# ESP32_zigbee_zwaveV1.net
KiCad netlist of a schematic drawn in EAGLE
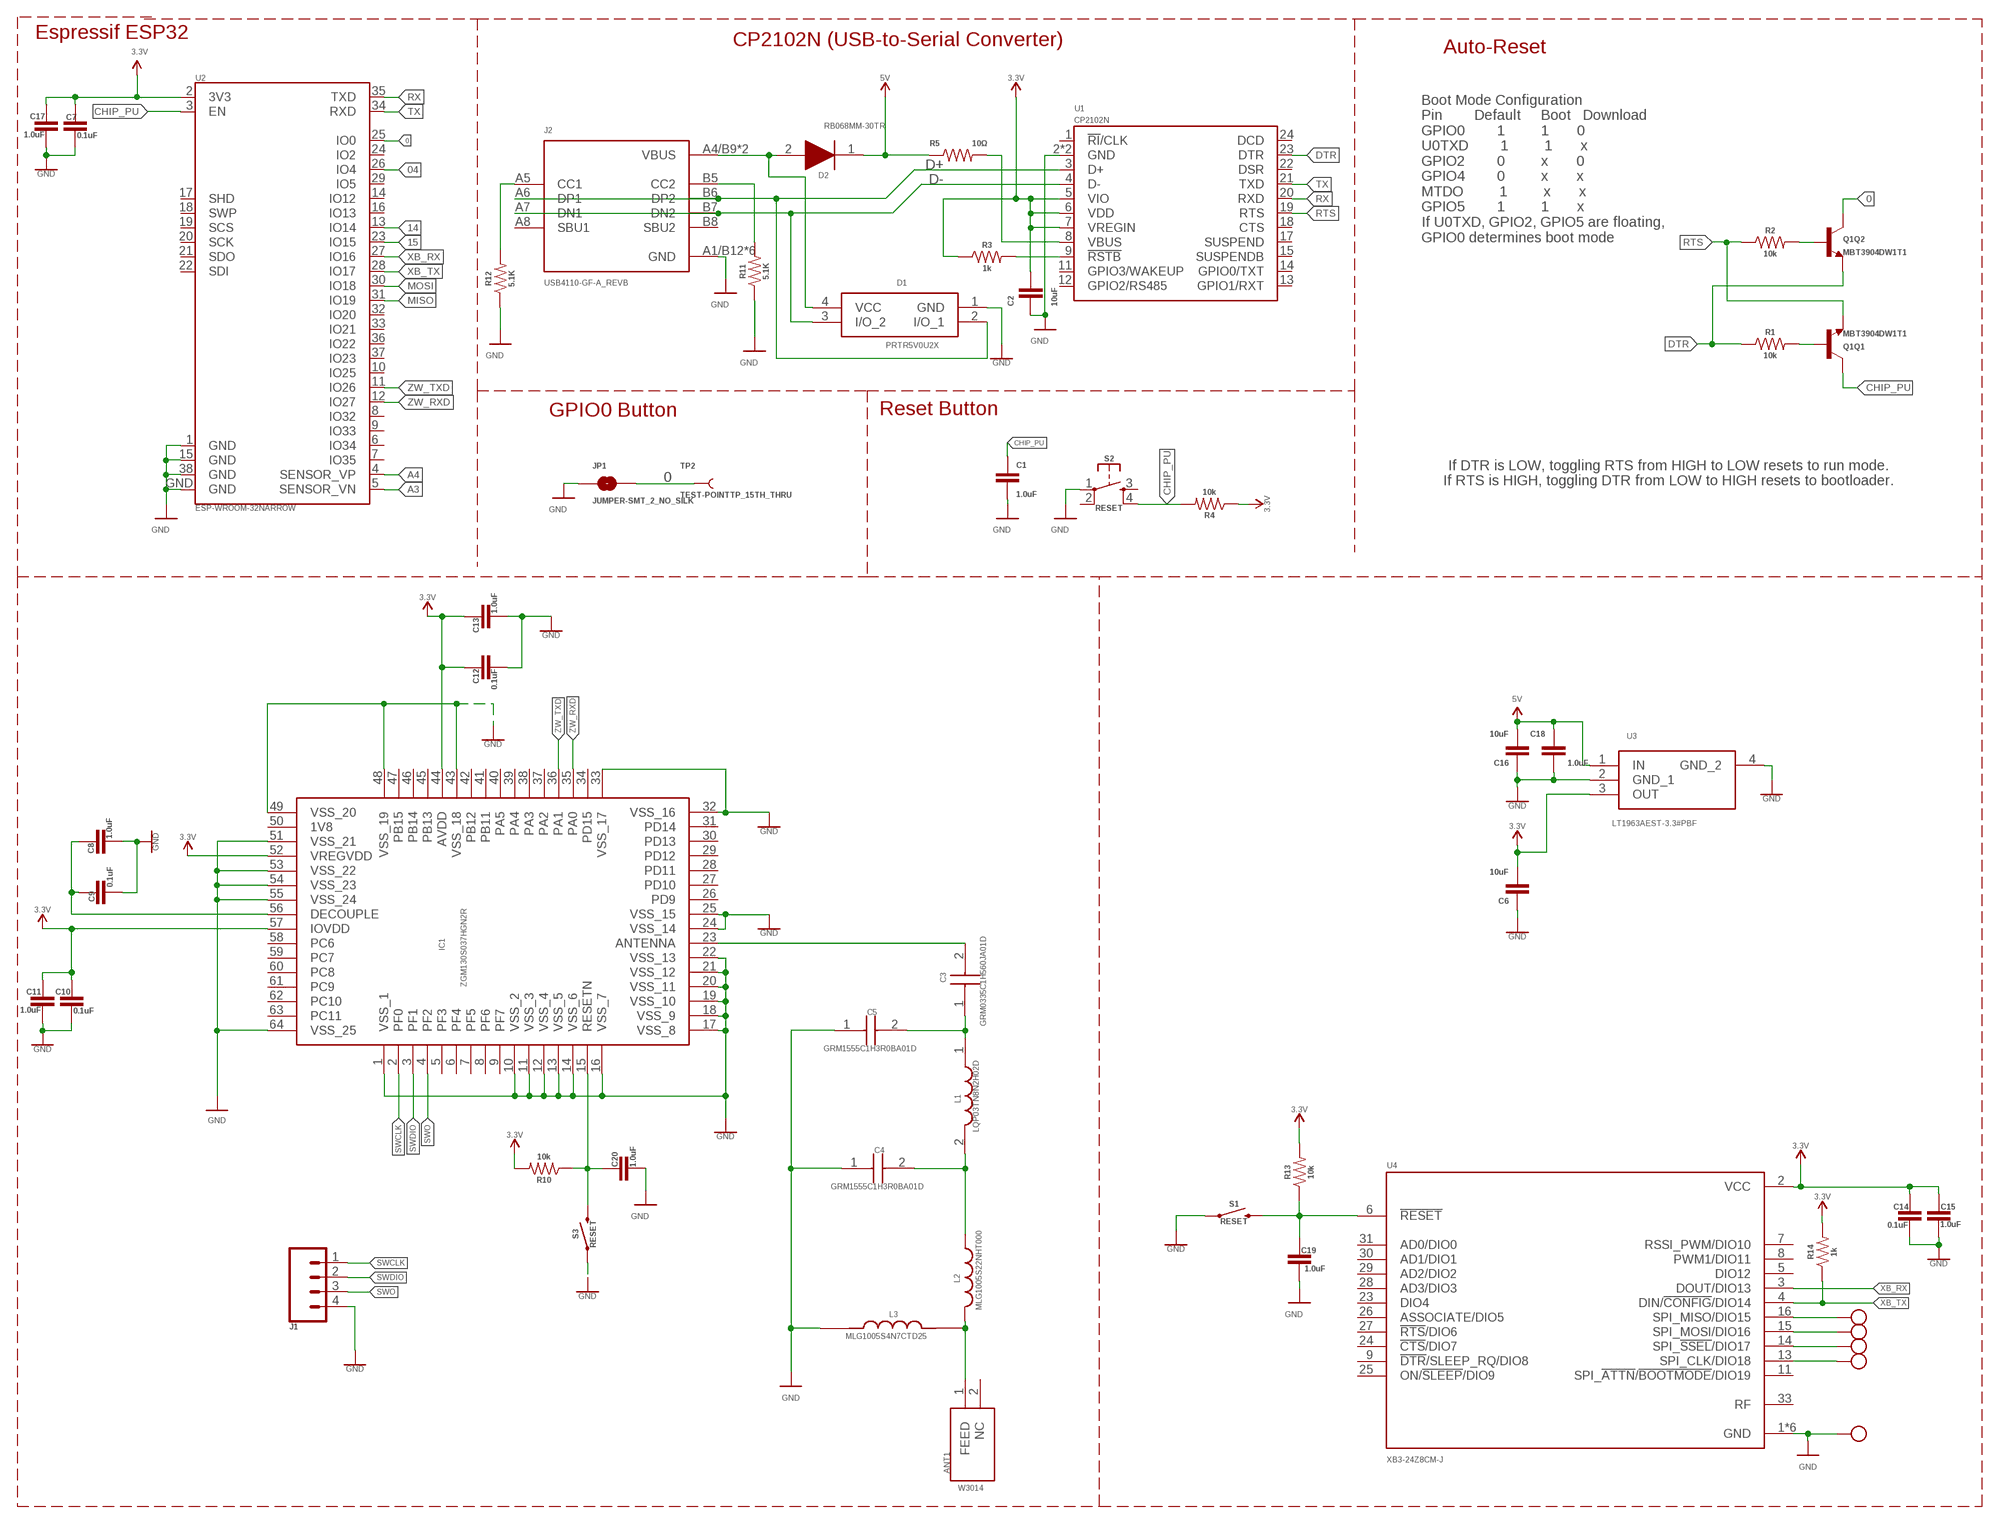
[diagram p0: schematic, sheet 1]

(export (version "E")
  (design (tool "Eeschema 10.0.6"))
  (components
    (comp (ref "ANT1")
      (value "W3014")
      (footprint "eagle-import:ANTC10032X155N")
      (fields (field (name "MOUSER_PART_NUMBER") "673-W3014"))
      (libsource (lib "eagle-import") (part "W3014"))
    )
    (comp (ref "C1")
      (value "1.0uF")
      (footprint "eagle-import:0402-TIGHT")
      (libsource (lib "eagle-import") (part "1.0UF-0402T-16V-10%"))
    )
    (comp (ref "C2")
      (value "10uF")
      (footprint "eagle-import:0402-TIGHT")
      (libsource (lib "eagle-import") (part "10UF-0402T-6.3V-20%"))
    )
    (comp (ref "C3")
      (value "GRM0335C1H560JA01D")
      (footprint "eagle-import:CAPC0603X33N")
      (fields (field (name "MOUSER_PART_NUMBER") "81-GRM0335C1H560JA1D"))
      (libsource (lib "eagle-import") (part "GRM0335C1H560JA01D"))
    )
    (comp (ref "C4")
      (value "GRM1555C1H3R0BA01D")
      (footprint "eagle-import:CAPC1005X55N")
      (fields (field (name "MOUSER_PART_NUMBER") "81-GRM1555C1H3R0BA1D"))
      (libsource (lib "eagle-import") (part "GRM1555C1H3R0BA01D"))
    )
    (comp (ref "C5")
      (value "GRM1555C1H3R0BA01D")
      (footprint "eagle-import:CAPC1005X55N")
      (fields (field (name "MOUSER_PART_NUMBER") "81-GRM1555C1H3R0BA1D"))
      (libsource (lib "eagle-import") (part "GRM1555C1H3R0BA01D"))
    )
    (comp (ref "C6")
      (value "10uF")
      (footprint "eagle-import:0805")
      (libsource (lib "eagle-import") (part "10UF-0805-25V-10%"))
    )
    (comp (ref "C7")
      (value "0.1uF")
      (footprint "eagle-import:0402-TIGHT")
      (libsource (lib "eagle-import") (part "0.1UF-0402T-6.3V-10%-X7R"))
    )
    (comp (ref "C8")
      (value "1.0uF")
      (footprint "eagle-import:0402-TIGHT")
      (libsource (lib "eagle-import") (part "1.0UF-0402T-16V-10%"))
    )
    (comp (ref "C9")
      (value "0.1uF")
      (footprint "eagle-import:0402-TIGHT")
      (libsource (lib "eagle-import") (part "0.1UF-0402T-6.3V-10%-X7R"))
    )
    (comp (ref "C10")
      (value "0.1uF")
      (footprint "eagle-import:0402-TIGHT")
      (libsource (lib "eagle-import") (part "0.1UF-0402T-6.3V-10%-X7R"))
    )
    (comp (ref "C11")
      (value "1.0uF")
      (footprint "eagle-import:0402-TIGHT")
      (libsource (lib "eagle-import") (part "1.0UF-0402T-16V-10%"))
    )
    (comp (ref "C12")
      (value "0.1uF")
      (footprint "eagle-import:0402-TIGHT")
      (libsource (lib "eagle-import") (part "0.1UF-0402T-6.3V-10%-X7R"))
    )
    (comp (ref "C13")
      (value "1.0uF")
      (footprint "eagle-import:0402-TIGHT")
      (libsource (lib "eagle-import") (part "1.0UF-0402T-16V-10%"))
    )
    (comp (ref "C14")
      (value "0.1uF")
      (footprint "eagle-import:0402-TIGHT")
      (libsource (lib "eagle-import") (part "0.1UF-0402T-6.3V-10%-X7R"))
    )
    (comp (ref "C15")
      (value "1.0uF")
      (footprint "eagle-import:0402-TIGHT")
      (libsource (lib "eagle-import") (part "1.0UF-0402T-16V-10%"))
    )
    (comp (ref "C16")
      (value "10uF")
      (footprint "eagle-import:0805")
      (libsource (lib "eagle-import") (part "10UF-0805-25V-10%"))
    )
    (comp (ref "C17")
      (value "1.0uF")
      (footprint "eagle-import:0402-TIGHT")
      (libsource (lib "eagle-import") (part "1.0UF-0402T-16V-10%"))
    )
    (comp (ref "C18")
      (value "1.0uF")
      (footprint "eagle-import:0402-TIGHT")
      (libsource (lib "eagle-import") (part "1.0UF-0402T-16V-10%"))
    )
    (comp (ref "C19")
      (value "1.0uF")
      (footprint "eagle-import:0402-TIGHT")
      (libsource (lib "eagle-import") (part "1.0UF-0402T-16V-10%"))
    )
    (comp (ref "C20")
      (value "1.0uF")
      (footprint "eagle-import:0402-TIGHT")
      (libsource (lib "eagle-import") (part "1.0UF-0402T-16V-10%"))
    )
    (comp (ref "D1")
      (value "PRTR5V0U2X")
      (footprint "eagle-import:PRTR5V0U2X")
      (libsource (lib "eagle-import") (part "PRTR5V0U2X"))
    )
    (comp (ref "D2")
      (value "RB068MM-30TR")
      (footprint "eagle-import:SODFL3516X90N")
      (fields (field (name "MOUSER_PART_NUMBER") "755-RB068MM-30TR"))
      (libsource (lib "eagle-import") (part "RB068MM-30TR"))
    )
    (comp (ref "IC1")
      (value "ZGM130S037HGN2R")
      (footprint "eagle-import:ZGM130S037HGN2R")
      (fields (field (name "MOUSER_PART_NUMBER") "634-ZGM130S037HGN2R"))
      (libsource (lib "eagle-import") (part "ZGM130S037HGN2R"))
    )
    (comp (ref "J1")
      (value "CONN_041X04_NO_SILK")
      (footprint "eagle-import:1X04_NO_SILK")
      (libsource (lib "eagle-import") (part "CONN_041X04_NO_SILK"))
    )
    (comp (ref "J2")
      (value "USB4110-GF-A_REVB")
      (footprint "eagle-import:GCT_USB4110-GF-A_REVB")
      (fields (field (name "MF") "GCT") (field (name "MP") "USB4110-GF-A"))
      (libsource (lib "eagle-import") (part "USB4110-GF-A_REVB"))
    )
    (comp (ref "JP1")
      (value "JUMPER-SMT_2_NO_SILK")
      (footprint "eagle-import:SMT-JUMPER_2_NO_SILK")
      (libsource (lib "eagle-import") (part "JUMPER-SMT_2_NO_SILK"))
    )
    (comp (ref "L1")
      (value "LQP03TN8N2H02D")
      (footprint "eagle-import:LQP03TG3N1B02D")
      (fields (field (name "MOUSER_PART_NUMBER") "81-LQP03TN8N2H02D"))
      (libsource (lib "eagle-import") (part "LQP03TN8N2H02D"))
    )
    (comp (ref "L2")
      (value "MLG1005S22NHT000")
      (footprint "eagle-import:INDC1005X55N")
      (fields (field (name "MF") "TDK"))
      (libsource (lib "eagle-import") (part "MLG1005S22NHT000"))
    )
    (comp (ref "L3")
      (value "MLG1005S4N7CTD25")
      (footprint "eagle-import:INDC1005X55N")
      (fields (field (name "MF") "TDK"))
      (libsource (lib "eagle-import") (part "MLG1005S4N7CTD25"))
    )
    (comp (ref "Q1")
      (value "MBT3904DW1T1")
      (footprint "eagle-import:SC70-6")
      (libsource (lib "eagle-import") (part "TRANS_NPN_DUAL-MBT3904DW1T1"))
    )
    (comp (ref "R1")
      (value "10k")
      (footprint "eagle-import:0402-TIGHT")
      (libsource (lib "eagle-import") (part "10KOHM-0402T-1/16W-1%"))
    )
    (comp (ref "R2")
      (value "10k")
      (footprint "eagle-import:0402-TIGHT")
      (libsource (lib "eagle-import") (part "10KOHM-0402T-1/16W-1%"))
    )
    (comp (ref "R3")
      (value "1k")
      (footprint "eagle-import:0402-TIGHT")
      (libsource (lib "eagle-import") (part "1KOHM-0402T-1/16W-1%"))
    )
    (comp (ref "R4")
      (value "10k")
      (footprint "eagle-import:0402-TIGHT")
      (libsource (lib "eagle-import") (part "10KOHM-0402T-1/16W-1%"))
    )
    (comp (ref "R5")
      (value "10Ω")
      (footprint "eagle-import:0402-TIGHT")
      (libsource (lib "eagle-import") (part "10OHM-0402-1/16W-5%"))
    )
    (comp (ref "R10")
      (value "10k")
      (footprint "eagle-import:0402-TIGHT")
      (libsource (lib "eagle-import") (part "10KOHM-0402-1/10W-0.1%"))
    )
    (comp (ref "R11")
      (value "5.1K")
      (footprint "eagle-import:0402-TIGHT")
      (libsource (lib "eagle-import") (part "RESISTOR0402T"))
    )
    (comp (ref "R12")
      (value "5.1K")
      (footprint "eagle-import:0402-TIGHT")
      (libsource (lib "eagle-import") (part "RESISTOR0402T"))
    )
    (comp (ref "R13")
      (value "10k")
      (footprint "eagle-import:0402-TIGHT")
      (libsource (lib "eagle-import") (part "10KOHM-0402-1/10W-0.1%"))
    )
    (comp (ref "R14")
      (value "1k")
      (footprint "eagle-import:0402-TIGHT")
      (libsource (lib "eagle-import") (part "1KOHM-0402T-1/16W-1%"))
    )
    (comp (ref "S1")
      (value "RESET")
      (footprint "eagle-import:TACTILE_SWITCH_SMD_4.6X2.8MM")
      (libsource (lib "eagle-import") (part "MOMENTARY-SWITCH-SPST-SMD-4.6X2.8MM"))
    )
    (comp (ref "S2")
      (value "RESET")
      (footprint "eagle-import:TACTILE_SWITCH_SMD_4.6X2.8MM")
      (libsource (lib "eagle-import") (part "MOMENTARY-SWITCH-SPST-2-SMD-4.6X2.8MM"))
    )
    (comp (ref "S3")
      (value "RESET")
      (footprint "eagle-import:TACTILE_SWITCH_SMD_4.6X2.8MM")
      (libsource (lib "eagle-import") (part "MOMENTARY-SWITCH-SPST-SMD-4.6X2.8MM"))
    )
    (comp (ref "TP1")
      (value "TESTPOINT1.5X2.0MM_NOCREAM")
      (footprint "eagle-import:PAD-1.5X2.0")
      (libsource (lib "eagle-import") (part "TESTPOINT1.5X2.0MM_NOCREAM"))
    )
    (comp (ref "TP2")
      (value "TEST-POINTTP_15TH_THRU")
      (footprint "eagle-import:TP_15TH")
      (libsource (lib "eagle-import") (part "TEST-POINTTP_15TH_THRU"))
    )
    (comp (ref "TP3")
      (value "TESTPOINT1.5X2.0MM_NOCREAM")
      (footprint "eagle-import:PAD-1.5X2.0")
      (libsource (lib "eagle-import") (part "TESTPOINT1.5X2.0MM_NOCREAM"))
    )
    (comp (ref "TP4")
      (value "TESTPOINT1.5X2.0MM_NOCREAM")
      (footprint "eagle-import:PAD-1.5X2.0")
      (libsource (lib "eagle-import") (part "TESTPOINT1.5X2.0MM_NOCREAM"))
    )
    (comp (ref "TP5")
      (value "TESTPOINT1.5X2.0MM_NOCREAM")
      (footprint "eagle-import:PAD-1.5X2.0")
      (libsource (lib "eagle-import") (part "TESTPOINT1.5X2.0MM_NOCREAM"))
    )
    (comp (ref "TP6")
      (value "TESTPOINT1.5X2.0MM_NOCREAM")
      (footprint "eagle-import:PAD-1.5X2.0")
      (libsource (lib "eagle-import") (part "TESTPOINT1.5X2.0MM_NOCREAM"))
    )
    (comp (ref "U1")
      (value "CP2102N")
      (footprint "eagle-import:QFN24")
      (libsource (lib "eagle-import") (part "CP2102N"))
    )
    (comp (ref "U2")
      (value "ESP-WROOM-32NARROW")
      (footprint "eagle-import:ESP-WROOM-32-NARROW")
      (fields (field (name "PROD_ID") "IC-13849"))
      (libsource (lib "eagle-import") (part "ESP-WROOM-32NARROW"))
    )
    (comp (ref "U3")
      (value "LT1963AEST-3.3#PBF")
      (footprint "eagle-import:SOT230P700X180-4N")
      (fields (field (name "MOUSER_PART_NUMBER") "584-1963AEST-3.3PBF"))
      (libsource (lib "eagle-import") (part "LT1963AEST-3.3#PBF"))
    )
    (comp (ref "U4")
      (value "XB3-24Z8CM-J")
      (footprint "eagle-import:XCVR_XB3-24Z8CM-J")
      (fields (field (name "MF") "Digi International"))
      (libsource (lib "eagle-import") (part "XB3-24Z8CM-J"))
    )
  )
  (nets
    (net (code "1") (name "/D+") (class "Default")
      (node (ref "D1") (pin "2") (pinfunction "I/O_1_2") (pintype "bidirectional"))
      (node (ref "J2") (pin "A6") (pinfunction "DP1_A6") (pintype "bidirectional"))
      (node (ref "J2") (pin "B6") (pinfunction "DP2_B6") (pintype "bidirectional"))
      (node (ref "U1") (pin "3") (pinfunction "D+_3") (pintype "bidirectional"))
    )
    (net (code "2") (name "/D-") (class "Default")
      (node (ref "D1") (pin "3") (pinfunction "I/O_2_3") (pintype "bidirectional"))
      (node (ref "J2") (pin "A7") (pinfunction "DN1_A7") (pintype "bidirectional"))
      (node (ref "J2") (pin "B7") (pinfunction "DN2_B7") (pintype "bidirectional"))
      (node (ref "U1") (pin "4") (pinfunction "D-_4") (pintype "bidirectional"))
    )
    (net (code "3") (name "0") (class "Default")
      (node (ref "JP1") (pin "2") (pinfunction "2_2") (pintype "passive"))
      (node (ref "Q1") (pin "6") (pinfunction "C_6") (pintype "passive"))
      (node (ref "TP2") (pin "P$1") (pinfunction "1_P$1") (pintype "bidirectional"))
      (node (ref "U2") (pin "25") (pinfunction "IO0_25") (pintype "bidirectional"))
    )
    (net (code "4") (name "3.3V?") (class "Default")
      (node (ref "C10") (pin "1") (pinfunction "1_1") (pintype "passive"))
      (node (ref "C11") (pin "2") (pinfunction "2_2") (pintype "passive"))
      (node (ref "C12") (pin "1") (pinfunction "1_1") (pintype "passive"))
      (node (ref "C13") (pin "2") (pinfunction "2_2") (pintype "passive"))
      (node (ref "C14") (pin "1") (pinfunction "1_1") (pintype "passive"))
      (node (ref "C15") (pin "2") (pinfunction "2_2") (pintype "passive"))
      (node (ref "C17") (pin "2") (pinfunction "2_2") (pintype "passive"))
      (node (ref "C2") (pin "1") (pinfunction "1_1") (pintype "passive"))
      (node (ref "C6") (pin "2") (pinfunction "2_2") (pintype "passive"))
      (node (ref "C7") (pin "1") (pinfunction "1_1") (pintype "passive"))
      (node (ref "IC1") (pin "44") (pinfunction "AVDD_44") (pintype "bidirectional"))
      (node (ref "IC1") (pin "52") (pinfunction "VREGVDD_52") (pintype "bidirectional"))
      (node (ref "IC1") (pin "57") (pinfunction "IOVDD_57") (pintype "bidirectional"))
      (node (ref "R10") (pin "2") (pinfunction "2_2") (pintype "passive"))
      (node (ref "R13") (pin "2") (pinfunction "2_2") (pintype "passive"))
      (node (ref "R14") (pin "2") (pinfunction "2_2") (pintype "passive"))
      (node (ref "R3") (pin "1") (pinfunction "1_1") (pintype "passive"))
      (node (ref "R4") (pin "1") (pinfunction "1_1") (pintype "passive"))
      (node (ref "U1") (pin "5") (pinfunction "VIO_5") (pintype "bidirectional"))
      (node (ref "U1") (pin "6") (pinfunction "VDD_6") (pintype "bidirectional"))
      (node (ref "U1") (pin "7") (pinfunction "VREGIN_7") (pintype "bidirectional"))
      (node (ref "U2") (pin "2") (pinfunction "3V3_2") (pintype "bidirectional"))
      (node (ref "U3") (pin "3") (pinfunction "OUT_3") (pintype "bidirectional"))
      (node (ref "U4") (pin "2") (pinfunction "VCC_2") (pintype "power_in"))
    )
    (net (code "5") (name "04") (class "Default")
      (node (ref "U2") (pin "26") (pinfunction "IO4_26") (pintype "bidirectional"))
    )
    (net (code "6") (name "5V") (class "Default")
      (node (ref "C16") (pin "2") (pinfunction "2_2") (pintype "passive"))
      (node (ref "C18") (pin "2") (pinfunction "2_2") (pintype "passive"))
      (node (ref "D2") (pin "1") (pinfunction "K_1") (pintype "bidirectional"))
      (node (ref "R5") (pin "1") (pinfunction "1_1") (pintype "passive"))
      (node (ref "U3") (pin "1") (pinfunction "IN_1") (pintype "bidirectional"))
    )
    (net (code "7") (name "14") (class "Default")
      (node (ref "U2") (pin "13") (pinfunction "IO14_13") (pintype "bidirectional"))
    )
    (net (code "8") (name "15") (class "Default")
      (node (ref "U2") (pin "23") (pinfunction "IO15_23") (pintype "bidirectional"))
    )
    (net (code "9") (name "A3") (class "Default")
      (node (ref "U2") (pin "5") (pinfunction "SENSOR_VN_5") (pintype "bidirectional"))
    )
    (net (code "10") (name "A4") (class "Default")
      (node (ref "U2") (pin "4") (pinfunction "SENSOR_VP_4") (pintype "bidirectional"))
    )
    (net (code "11") (name "CHIP_PU") (class "Default")
      (node (ref "C1") (pin "1") (pinfunction "1_1") (pintype "passive"))
      (node (ref "Q1") (pin "3") (pinfunction "C_3") (pintype "passive"))
      (node (ref "R4") (pin "2") (pinfunction "2_2") (pintype "passive"))
      (node (ref "S2") (pin "4") (pinfunction "4_4") (pintype "passive"))
      (node (ref "U2") (pin "3") (pinfunction "EN_3") (pintype "bidirectional"))
    )
    (net (code "12") (name "DTR") (class "Default")
      (node (ref "Q1") (pin "1") (pinfunction "E_1") (pintype "passive"))
      (node (ref "R1") (pin "1") (pinfunction "1_1") (pintype "passive"))
      (node (ref "U1") (pin "23") (pinfunction "DTR_23") (pintype "bidirectional"))
    )
    (net (code "13") (name "GND") (class "Default")
      (node (ref "C1") (pin "2") (pinfunction "2_2") (pintype "passive"))
      (node (ref "C10") (pin "2") (pinfunction "2_2") (pintype "passive"))
      (node (ref "C11") (pin "1") (pinfunction "1_1") (pintype "passive"))
      (node (ref "C12") (pin "2") (pinfunction "2_2") (pintype "passive"))
      (node (ref "C13") (pin "1") (pinfunction "1_1") (pintype "passive"))
      (node (ref "C14") (pin "2") (pinfunction "2_2") (pintype "passive"))
      (node (ref "C15") (pin "1") (pinfunction "1_1") (pintype "passive"))
      (node (ref "C16") (pin "1") (pinfunction "1_1") (pintype "passive"))
      (node (ref "C17") (pin "1") (pinfunction "1_1") (pintype "passive"))
      (node (ref "C18") (pin "1") (pinfunction "1_1") (pintype "passive"))
      (node (ref "C19") (pin "2") (pinfunction "2_2") (pintype "passive"))
      (node (ref "C2") (pin "2") (pinfunction "2_2") (pintype "passive"))
      (node (ref "C20") (pin "2") (pinfunction "2_2") (pintype "passive"))
      (node (ref "C4") (pin "1") (pinfunction "1_1") (pintype "bidirectional"))
      (node (ref "C5") (pin "1") (pinfunction "1_1") (pintype "bidirectional"))
      (node (ref "C6") (pin "1") (pinfunction "1_1") (pintype "passive"))
      (node (ref "C7") (pin "2") (pinfunction "2_2") (pintype "passive"))
      (node (ref "C8") (pin "1") (pinfunction "1_1") (pintype "passive"))
      (node (ref "C9") (pin "2") (pinfunction "2_2") (pintype "passive"))
      (node (ref "D1") (pin "1") (pinfunction "GND_1") (pintype "bidirectional"))
      (node (ref "IC1") (pin "1") (pinfunction "VSS_1_1") (pintype "bidirectional"))
      (node (ref "IC1") (pin "10") (pinfunction "VSS_2_10") (pintype "bidirectional"))
      (node (ref "IC1") (pin "11") (pinfunction "VSS_3_11") (pintype "bidirectional"))
      (node (ref "IC1") (pin "12") (pinfunction "VSS_4_12") (pintype "bidirectional"))
      (node (ref "IC1") (pin "13") (pinfunction "VSS_5_13") (pintype "bidirectional"))
      (node (ref "IC1") (pin "14") (pinfunction "VSS_6_14") (pintype "bidirectional"))
      (node (ref "IC1") (pin "16") (pinfunction "VSS_7_16") (pintype "bidirectional"))
      (node (ref "IC1") (pin "17") (pinfunction "VSS_8_17") (pintype "bidirectional"))
      (node (ref "IC1") (pin "18") (pinfunction "VSS_9_18") (pintype "bidirectional"))
      (node (ref "IC1") (pin "19") (pinfunction "VSS_10_19") (pintype "bidirectional"))
      (node (ref "IC1") (pin "20") (pinfunction "VSS_11_20") (pintype "bidirectional"))
      (node (ref "IC1") (pin "21") (pinfunction "VSS_12_21") (pintype "bidirectional"))
      (node (ref "IC1") (pin "22") (pinfunction "VSS_13_22") (pintype "bidirectional"))
      (node (ref "IC1") (pin "24") (pinfunction "VSS_14_24") (pintype "bidirectional"))
      (node (ref "IC1") (pin "25") (pinfunction "VSS_15_25") (pintype "bidirectional"))
      (node (ref "IC1") (pin "32") (pinfunction "VSS_16_32") (pintype "bidirectional"))
      (node (ref "IC1") (pin "33") (pinfunction "VSS_17_33") (pintype "bidirectional"))
      (node (ref "IC1") (pin "43") (pinfunction "VSS_18_43") (pintype "bidirectional"))
      (node (ref "IC1") (pin "48") (pinfunction "VSS_19_48") (pintype "bidirectional"))
      (node (ref "IC1") (pin "49") (pinfunction "VSS_20_49") (pintype "bidirectional"))
      (node (ref "IC1") (pin "51") (pinfunction "VSS_21_51") (pintype "bidirectional"))
      (node (ref "IC1") (pin "53") (pinfunction "VSS_22_53") (pintype "bidirectional"))
      (node (ref "IC1") (pin "54") (pinfunction "VSS_23_54") (pintype "bidirectional"))
      (node (ref "IC1") (pin "55") (pinfunction "VSS_24_55") (pintype "bidirectional"))
      (node (ref "IC1") (pin "64") (pinfunction "VSS_25_64") (pintype "bidirectional"))
      (node (ref "J1") (pin "4") (pinfunction "4_4") (pintype "passive"))
      (node (ref "J2") (pin "A1/B12") (pinfunction "GND_A1/B12") (pintype "power_in"))
      (node (ref "J2") (pin "B1/A12") (pinfunction "GND_B1/A12") (pintype "power_in"))
      (node (ref "J2") (pin "S1") (pinfunction "GND_S1") (pintype "power_in"))
      (node (ref "J2") (pin "S2") (pinfunction "GND_S2") (pintype "power_in"))
      (node (ref "J2") (pin "S3") (pinfunction "GND_S3") (pintype "power_in"))
      (node (ref "J2") (pin "S4") (pinfunction "GND_S4") (pintype "power_in"))
      (node (ref "JP1") (pin "1") (pinfunction "1_1") (pintype "passive"))
      (node (ref "L3") (pin "1") (pinfunction "1_1") (pintype "passive"))
      (node (ref "R11") (pin "1") (pinfunction "1_1") (pintype "passive"))
      (node (ref "R12") (pin "1") (pinfunction "1_1") (pintype "passive"))
      (node (ref "S1") (pin "1") (pinfunction "1_1") (pintype "passive"))
      (node (ref "S1") (pin "2") (pinfunction "1_2") (pintype "passive"))
      (node (ref "S2") (pin "1") (pinfunction "1_1") (pintype "passive"))
      (node (ref "S3") (pin "1") (pinfunction "1_1") (pintype "passive"))
      (node (ref "S3") (pin "2") (pinfunction "1_2") (pintype "passive"))
      (node (ref "TP6") (pin "P$1") (pinfunction "P$1_P$1") (pintype "bidirectional"))
      (node (ref "U1") (pin "2") (pinfunction "GND_2") (pintype "bidirectional"))
      (node (ref "U1") (pin "PAD") (pinfunction "GND_PAD") (pintype "bidirectional"))
      (node (ref "U2") (pin "1") (pinfunction "GND_1") (pintype "bidirectional"))
      (node (ref "U2") (pin "15") (pinfunction "GND_15") (pintype "bidirectional"))
      (node (ref "U2") (pin "38") (pinfunction "GND_38") (pintype "bidirectional"))
      (node (ref "U2") (pin "GND") (pinfunction "GND_GND") (pintype "bidirectional"))
      (node (ref "U3") (pin "2") (pinfunction "GND_1_2") (pintype "bidirectional"))
      (node (ref "U3") (pin "4") (pinfunction "GND_2_4") (pintype "bidirectional"))
      (node (ref "U4") (pin "1") (pinfunction "GND_1") (pintype "power_in"))
      (node (ref "U4") (pin "10") (pinfunction "GND_10") (pintype "power_in"))
      (node (ref "U4") (pin "12") (pinfunction "GND_12") (pintype "power_in"))
      (node (ref "U4") (pin "21") (pinfunction "GND_21") (pintype "power_in"))
      (node (ref "U4") (pin "32") (pinfunction "GND_32") (pintype "power_in"))
      (node (ref "U4") (pin "34") (pinfunction "GND_34") (pintype "power_in"))
    )
    (net (code "14") (name "MISO") (class "Default")
      (node (ref "U2") (pin "31") (pinfunction "IO19_31") (pintype "bidirectional"))
    )
    (net (code "15") (name "MOSI") (class "Default")
      (node (ref "U2") (pin "30") (pinfunction "IO18_30") (pintype "bidirectional"))
    )
    (net (code "16") (name "Net-(ANT1-FEED)") (class "Default")
      (node (ref "ANT1") (pin "1") (pinfunction "FEED_1") (pintype "input"))
      (node (ref "L2") (pin "2") (pinfunction "2_2") (pintype "passive"))
      (node (ref "L3") (pin "2") (pinfunction "2_2") (pintype "passive"))
    )
    (net (code "17") (name "Net-(C3-Pad1)") (class "Default")
      (node (ref "C3") (pin "1") (pinfunction "1_1") (pintype "bidirectional"))
      (node (ref "C5") (pin "2") (pinfunction "2_2") (pintype "bidirectional"))
      (node (ref "L1") (pin "1") (pinfunction "1_1") (pintype "bidirectional"))
    )
    (net (code "18") (name "Net-(C4-Pad2)") (class "Default")
      (node (ref "C4") (pin "2") (pinfunction "2_2") (pintype "bidirectional"))
      (node (ref "L1") (pin "2") (pinfunction "2_2") (pintype "bidirectional"))
      (node (ref "L2") (pin "1") (pinfunction "1_1") (pintype "passive"))
    )
    (net (code "19") (name "Net-(D1-VCC)") (class "Default")
      (node (ref "D1") (pin "4") (pinfunction "VCC_4") (pintype "bidirectional"))
      (node (ref "D2") (pin "2") (pinfunction "A_2") (pintype "bidirectional"))
      (node (ref "J2") (pin "A4/B9") (pinfunction "VBUS_A4/B9") (pintype "power_in"))
      (node (ref "J2") (pin "B4/A9") (pinfunction "VBUS_B4/A9") (pintype "power_in"))
    )
    (net (code "20") (name "Net-(IC1-ANTENNA)") (class "Default")
      (node (ref "C3") (pin "2") (pinfunction "2_2") (pintype "bidirectional"))
      (node (ref "IC1") (pin "23") (pinfunction "ANTENNA_23") (pintype "bidirectional"))
    )
    (net (code "21") (name "Net-(IC1-DECOUPLE)") (class "Default")
      (node (ref "C8") (pin "2") (pinfunction "2_2") (pintype "passive"))
      (node (ref "C9") (pin "1") (pinfunction "1_1") (pintype "passive"))
      (node (ref "IC1") (pin "56") (pinfunction "DECOUPLE_56") (pintype "bidirectional"))
    )
    (net (code "22") (name "Net-(IC1-RESETN)") (class "Default")
      (node (ref "C20") (pin "1") (pinfunction "1_1") (pintype "passive"))
      (node (ref "IC1") (pin "15") (pinfunction "RESETN_15") (pintype "bidirectional"))
      (node (ref "R10") (pin "1") (pinfunction "1_1") (pintype "passive"))
      (node (ref "S3") (pin "3") (pinfunction "2_3") (pintype "passive"))
      (node (ref "S3") (pin "4") (pinfunction "2_4") (pintype "passive"))
    )
    (net (code "23") (name "Net-(J2-CC1)") (class "Default")
      (node (ref "J2") (pin "A5") (pinfunction "CC1_A5") (pintype "bidirectional"))
      (node (ref "R12") (pin "2") (pinfunction "2_2") (pintype "passive"))
    )
    (net (code "24") (name "Net-(J2-CC2)") (class "Default")
      (node (ref "J2") (pin "B5") (pinfunction "CC2_B5") (pintype "bidirectional"))
      (node (ref "R11") (pin "2") (pinfunction "2_2") (pintype "passive"))
    )
    (net (code "25") (name "Net-(Q1A-B)") (class "Default")
      (node (ref "Q1") (pin "5") (pinfunction "B_5") (pintype "passive"))
      (node (ref "R1") (pin "2") (pinfunction "2_2") (pintype "passive"))
    )
    (net (code "26") (name "Net-(Q1B-B)") (class "Default")
      (node (ref "Q1") (pin "2") (pinfunction "B_2") (pintype "passive"))
      (node (ref "R2") (pin "2") (pinfunction "2_2") (pintype "passive"))
    )
    (net (code "27") (name "Net-(U1-VBUS)") (class "Default")
      (node (ref "R5") (pin "2") (pinfunction "2_2") (pintype "passive"))
      (node (ref "U1") (pin "8") (pinfunction "VBUS_8") (pintype "bidirectional"))
    )
    (net (code "28") (name "Net-(U1-~{RSTB})") (class "Default")
      (node (ref "R3") (pin "2") (pinfunction "2_2") (pintype "passive"))
      (node (ref "U1") (pin "9") (pinfunction "~{RSTB}_9") (pintype "bidirectional"))
    )
    (net (code "29") (name "Net-(U4-SPI_CLK{slash}DIO18)") (class "Default")
      (node (ref "TP4") (pin "P$1") (pinfunction "P$1_P$1") (pintype "bidirectional"))
      (node (ref "U4") (pin "13") (pinfunction "SPI_CLK/DIO18_13") (pintype "bidirectional"))
    )
    (net (code "30") (name "Net-(U4-SPI_MISO{slash}DIO15)") (class "Default")
      (node (ref "TP5") (pin "P$1") (pinfunction "P$1_P$1") (pintype "bidirectional"))
      (node (ref "U4") (pin "16") (pinfunction "SPI_MISO/DIO15_16") (pintype "bidirectional"))
    )
    (net (code "31") (name "Net-(U4-SPI_MOSI{slash}DIO16)") (class "Default")
      (node (ref "TP1") (pin "P$1") (pinfunction "P$1_P$1") (pintype "bidirectional"))
      (node (ref "U4") (pin "15") (pinfunction "SPI_MOSI/DIO16_15") (pintype "bidirectional"))
    )
    (net (code "32") (name "Net-(U4-SPI_~{SSEL}{slash}DIO17)") (class "Default")
      (node (ref "TP3") (pin "P$1") (pinfunction "P$1_P$1") (pintype "bidirectional"))
      (node (ref "U4") (pin "14") (pinfunction "SPI_~{SSEL}/DIO17_14") (pintype "bidirectional"))
    )
    (net (code "33") (name "Net-(U4-~{RESET})") (class "Default")
      (node (ref "C19") (pin "1") (pinfunction "1_1") (pintype "passive"))
      (node (ref "R13") (pin "1") (pinfunction "1_1") (pintype "passive"))
      (node (ref "S1") (pin "3") (pinfunction "2_3") (pintype "passive"))
      (node (ref "S1") (pin "4") (pinfunction "2_4") (pintype "passive"))
      (node (ref "U4") (pin "6") (pinfunction "~{RESET}_6") (pintype "input"))
    )
    (net (code "34") (name "RTS") (class "Default")
      (node (ref "Q1") (pin "4") (pinfunction "E_4") (pintype "passive"))
      (node (ref "R2") (pin "1") (pinfunction "1_1") (pintype "passive"))
      (node (ref "U1") (pin "19") (pinfunction "RTS_19") (pintype "bidirectional"))
    )
    (net (code "35") (name "RX") (class "Default")
      (node (ref "U1") (pin "20") (pinfunction "RXD_20") (pintype "bidirectional"))
      (node (ref "U2") (pin "35") (pinfunction "TXD_35") (pintype "bidirectional"))
    )
    (net (code "36") (name "SWCLK") (class "Default")
      (node (ref "IC1") (pin "2") (pinfunction "PF0_2") (pintype "bidirectional"))
      (node (ref "J1") (pin "1") (pinfunction "1_1") (pintype "passive"))
    )
    (net (code "37") (name "SWDIO") (class "Default")
      (node (ref "IC1") (pin "3") (pinfunction "PF1_3") (pintype "bidirectional"))
      (node (ref "J1") (pin "2") (pinfunction "2_2") (pintype "passive"))
    )
    (net (code "38") (name "SWO") (class "Default")
      (node (ref "IC1") (pin "4") (pinfunction "PF2_4") (pintype "bidirectional"))
      (node (ref "J1") (pin "3") (pinfunction "3_3") (pintype "passive"))
    )
    (net (code "39") (name "TX") (class "Default")
      (node (ref "U1") (pin "21") (pinfunction "TXD_21") (pintype "bidirectional"))
      (node (ref "U2") (pin "34") (pinfunction "RXD_34") (pintype "bidirectional"))
    )
    (net (code "40") (name "XB_RX") (class "Default")
      (node (ref "U2") (pin "27") (pinfunction "IO16_27") (pintype "bidirectional"))
      (node (ref "U4") (pin "3") (pinfunction "DOUT/DIO13_3") (pintype "bidirectional"))
    )
    (net (code "41") (name "XB_TX") (class "Default")
      (node (ref "R14") (pin "1") (pinfunction "1_1") (pintype "passive"))
      (node (ref "U2") (pin "28") (pinfunction "IO17_28") (pintype "bidirectional"))
      (node (ref "U4") (pin "4") (pinfunction "DIN/~{CONFIG}/DIO14_4") (pintype "bidirectional"))
    )
    (net (code "42") (name "ZW_RXD") (class "Default")
      (node (ref "IC1") (pin "35") (pinfunction "PA0_35") (pintype "bidirectional"))
      (node (ref "U2") (pin "12") (pinfunction "IO27_12") (pintype "bidirectional"))
    )
    (net (code "43") (name "ZW_TXD") (class "Default")
      (node (ref "IC1") (pin "36") (pinfunction "PA1_36") (pintype "bidirectional"))
      (node (ref "U2") (pin "11") (pinfunction "IO26_11") (pintype "bidirectional"))
    )
    (net (code "44") (name "unconnected-(ANT1-NC-Pad2)") (class "Default")
      (node (ref "ANT1") (pin "2") (pinfunction "NC_2") (pintype "no_connect"))
    )
    (net (code "45") (name "unconnected-(IC1-1V8-Pad50)") (class "Default")
      (node (ref "IC1") (pin "50") (pinfunction "1V8_50") (pintype "bidirectional"))
    )
    (net (code "46") (name "unconnected-(IC1-PA2-Pad37)") (class "Default")
      (node (ref "IC1") (pin "37") (pinfunction "PA2_37") (pintype "bidirectional"))
    )
    (net (code "47") (name "unconnected-(IC1-PA3-Pad38)") (class "Default")
      (node (ref "IC1") (pin "38") (pinfunction "PA3_38") (pintype "bidirectional"))
    )
    (net (code "48") (name "unconnected-(IC1-PA4-Pad39)") (class "Default")
      (node (ref "IC1") (pin "39") (pinfunction "PA4_39") (pintype "bidirectional"))
    )
    (net (code "49") (name "unconnected-(IC1-PA5-Pad40)") (class "Default")
      (node (ref "IC1") (pin "40") (pinfunction "PA5_40") (pintype "bidirectional"))
    )
    (net (code "50") (name "unconnected-(IC1-PB11-Pad41)") (class "Default")
      (node (ref "IC1") (pin "41") (pinfunction "PB11_41") (pintype "bidirectional"))
    )
    (net (code "51") (name "unconnected-(IC1-PB12-Pad42)") (class "Default")
      (node (ref "IC1") (pin "42") (pinfunction "PB12_42") (pintype "bidirectional"))
    )
    (net (code "52") (name "unconnected-(IC1-PB13-Pad45)") (class "Default")
      (node (ref "IC1") (pin "45") (pinfunction "PB13_45") (pintype "bidirectional"))
    )
    (net (code "53") (name "unconnected-(IC1-PB14-Pad46)") (class "Default")
      (node (ref "IC1") (pin "46") (pinfunction "PB14_46") (pintype "bidirectional"))
    )
    (net (code "54") (name "unconnected-(IC1-PB15-Pad47)") (class "Default")
      (node (ref "IC1") (pin "47") (pinfunction "PB15_47") (pintype "bidirectional"))
    )
    (net (code "55") (name "unconnected-(IC1-PC6-Pad58)") (class "Default")
      (node (ref "IC1") (pin "58") (pinfunction "PC6_58") (pintype "bidirectional"))
    )
    (net (code "56") (name "unconnected-(IC1-PC7-Pad59)") (class "Default")
      (node (ref "IC1") (pin "59") (pinfunction "PC7_59") (pintype "bidirectional"))
    )
    (net (code "57") (name "unconnected-(IC1-PC8-Pad60)") (class "Default")
      (node (ref "IC1") (pin "60") (pinfunction "PC8_60") (pintype "bidirectional"))
    )
    (net (code "58") (name "unconnected-(IC1-PC9-Pad61)") (class "Default")
      (node (ref "IC1") (pin "61") (pinfunction "PC9_61") (pintype "bidirectional"))
    )
    (net (code "59") (name "unconnected-(IC1-PC10-Pad62)") (class "Default")
      (node (ref "IC1") (pin "62") (pinfunction "PC10_62") (pintype "bidirectional"))
    )
    (net (code "60") (name "unconnected-(IC1-PC11-Pad63)") (class "Default")
      (node (ref "IC1") (pin "63") (pinfunction "PC11_63") (pintype "bidirectional"))
    )
    (net (code "61") (name "unconnected-(IC1-PD9-Pad26)") (class "Default")
      (node (ref "IC1") (pin "26") (pinfunction "PD9_26") (pintype "bidirectional"))
    )
    (net (code "62") (name "unconnected-(IC1-PD10-Pad27)") (class "Default")
      (node (ref "IC1") (pin "27") (pinfunction "PD10_27") (pintype "bidirectional"))
    )
    (net (code "63") (name "unconnected-(IC1-PD11-Pad28)") (class "Default")
      (node (ref "IC1") (pin "28") (pinfunction "PD11_28") (pintype "bidirectional"))
    )
    (net (code "64") (name "unconnected-(IC1-PD12-Pad29)") (class "Default")
      (node (ref "IC1") (pin "29") (pinfunction "PD12_29") (pintype "bidirectional"))
    )
    (net (code "65") (name "unconnected-(IC1-PD13-Pad30)") (class "Default")
      (node (ref "IC1") (pin "30") (pinfunction "PD13_30") (pintype "bidirectional"))
    )
    (net (code "66") (name "unconnected-(IC1-PD14-Pad31)") (class "Default")
      (node (ref "IC1") (pin "31") (pinfunction "PD14_31") (pintype "bidirectional"))
    )
    (net (code "67") (name "unconnected-(IC1-PD15-Pad34)") (class "Default")
      (node (ref "IC1") (pin "34") (pinfunction "PD15_34") (pintype "bidirectional"))
    )
    (net (code "68") (name "unconnected-(IC1-PF3-Pad5)") (class "Default")
      (node (ref "IC1") (pin "5") (pinfunction "PF3_5") (pintype "bidirectional"))
    )
    (net (code "69") (name "unconnected-(IC1-PF4-Pad6)") (class "Default")
      (node (ref "IC1") (pin "6") (pinfunction "PF4_6") (pintype "bidirectional"))
    )
    (net (code "70") (name "unconnected-(IC1-PF5-Pad7)") (class "Default")
      (node (ref "IC1") (pin "7") (pinfunction "PF5_7") (pintype "bidirectional"))
    )
    (net (code "71") (name "unconnected-(IC1-PF6-Pad8)") (class "Default")
      (node (ref "IC1") (pin "8") (pinfunction "PF6_8") (pintype "bidirectional"))
    )
    (net (code "72") (name "unconnected-(IC1-PF7-Pad9)") (class "Default")
      (node (ref "IC1") (pin "9") (pinfunction "PF7_9") (pintype "bidirectional"))
    )
    (net (code "73") (name "unconnected-(J2-SBU1-PadA8)") (class "Default")
      (node (ref "J2") (pin "A8") (pinfunction "SBU1_A8") (pintype "bidirectional"))
    )
    (net (code "74") (name "unconnected-(J2-SBU2-PadB8)") (class "Default")
      (node (ref "J2") (pin "B8") (pinfunction "SBU2_B8") (pintype "bidirectional"))
    )
    (net (code "75") (name "unconnected-(S2-Pad2)") (class "Default")
      (node (ref "S2") (pin "2") (pinfunction "2_2") (pintype "passive"))
    )
    (net (code "76") (name "unconnected-(S2-Pad3)") (class "Default")
      (node (ref "S2") (pin "3") (pinfunction "3_3") (pintype "passive"))
    )
    (net (code "77") (name "unconnected-(U1-CTS-Pad18)") (class "Default")
      (node (ref "U1") (pin "18") (pinfunction "CTS_18") (pintype "bidirectional"))
    )
    (net (code "78") (name "unconnected-(U1-DCD-Pad24)") (class "Default")
      (node (ref "U1") (pin "24") (pinfunction "DCD_24") (pintype "bidirectional"))
    )
    (net (code "79") (name "unconnected-(U1-DSR-Pad22)") (class "Default")
      (node (ref "U1") (pin "22") (pinfunction "DSR_22") (pintype "bidirectional"))
    )
    (net (code "80") (name "unconnected-(U1-GPIO0{slash}TXT-Pad14)") (class "Default")
      (node (ref "U1") (pin "14") (pinfunction "GPIO0/TXT_14") (pintype "bidirectional"))
    )
    (net (code "81") (name "unconnected-(U1-GPIO1{slash}RXT-Pad13)") (class "Default")
      (node (ref "U1") (pin "13") (pinfunction "GPIO1/RXT_13") (pintype "bidirectional"))
    )
    (net (code "82") (name "unconnected-(U1-GPIO2{slash}RS485-Pad12)") (class "Default")
      (node (ref "U1") (pin "12") (pinfunction "GPIO2/RS485_12") (pintype "bidirectional"))
    )
    (net (code "83") (name "unconnected-(U1-GPIO3{slash}WAKEUP-Pad11)") (class "Default")
      (node (ref "U1") (pin "11") (pinfunction "GPIO3/WAKEUP_11") (pintype "bidirectional"))
    )
    (net (code "84") (name "unconnected-(U1-SUSPEND-Pad17)") (class "Default")
      (node (ref "U1") (pin "17") (pinfunction "SUSPEND_17") (pintype "bidirectional"))
    )
    (net (code "85") (name "unconnected-(U1-SUSPENDB-Pad15)") (class "Default")
      (node (ref "U1") (pin "15") (pinfunction "SUSPENDB_15") (pintype "bidirectional"))
    )
    (net (code "86") (name "unconnected-(U1-~{RI}{slash}CLK-Pad1)") (class "Default")
      (node (ref "U1") (pin "1") (pinfunction "~{RI}/CLK_1") (pintype "bidirectional"))
    )
    (net (code "87") (name "unconnected-(U2-IO2-Pad24)") (class "Default")
      (node (ref "U2") (pin "24") (pinfunction "IO2_24") (pintype "bidirectional"))
    )
    (net (code "88") (name "unconnected-(U2-IO5-Pad29)") (class "Default")
      (node (ref "U2") (pin "29") (pinfunction "IO5_29") (pintype "bidirectional"))
    )
    (net (code "89") (name "unconnected-(U2-IO12-Pad14)") (class "Default")
      (node (ref "U2") (pin "14") (pinfunction "IO12_14") (pintype "bidirectional"))
    )
    (net (code "90") (name "unconnected-(U2-IO13-Pad16)") (class "Default")
      (node (ref "U2") (pin "16") (pinfunction "IO13_16") (pintype "bidirectional"))
    )
    (net (code "91") (name "unconnected-(U2-IO20-Pad32)") (class "Default")
      (node (ref "U2") (pin "32") (pinfunction "IO20_32") (pintype "bidirectional"))
    )
    (net (code "92") (name "unconnected-(U2-IO21-Pad33)") (class "Default")
      (node (ref "U2") (pin "33") (pinfunction "IO21_33") (pintype "bidirectional"))
    )
    (net (code "93") (name "unconnected-(U2-IO22-Pad36)") (class "Default")
      (node (ref "U2") (pin "36") (pinfunction "IO22_36") (pintype "bidirectional"))
    )
    (net (code "94") (name "unconnected-(U2-IO23-Pad37)") (class "Default")
      (node (ref "U2") (pin "37") (pinfunction "IO23_37") (pintype "bidirectional"))
    )
    (net (code "95") (name "unconnected-(U2-IO25-Pad10)") (class "Default")
      (node (ref "U2") (pin "10") (pinfunction "IO25_10") (pintype "bidirectional"))
    )
    (net (code "96") (name "unconnected-(U2-IO32-Pad8)") (class "Default")
      (node (ref "U2") (pin "8") (pinfunction "IO32_8") (pintype "bidirectional"))
    )
    (net (code "97") (name "unconnected-(U2-IO33-Pad9)") (class "Default")
      (node (ref "U2") (pin "9") (pinfunction "IO33_9") (pintype "bidirectional"))
    )
    (net (code "98") (name "unconnected-(U2-IO34-Pad6)") (class "Default")
      (node (ref "U2") (pin "6") (pinfunction "IO34_6") (pintype "bidirectional"))
    )
    (net (code "99") (name "unconnected-(U2-IO35-Pad7)") (class "Default")
      (node (ref "U2") (pin "7") (pinfunction "IO35_7") (pintype "bidirectional"))
    )
    (net (code "100") (name "unconnected-(U2-SCK-Pad20)") (class "Default")
      (node (ref "U2") (pin "20") (pinfunction "SCK_20") (pintype "bidirectional"))
    )
    (net (code "101") (name "unconnected-(U2-SCS-Pad19)") (class "Default")
      (node (ref "U2") (pin "19") (pinfunction "SCS_19") (pintype "bidirectional"))
    )
    (net (code "102") (name "unconnected-(U2-SDI-Pad22)") (class "Default")
      (node (ref "U2") (pin "22") (pinfunction "SDI_22") (pintype "bidirectional"))
    )
    (net (code "103") (name "unconnected-(U2-SDO-Pad21)") (class "Default")
      (node (ref "U2") (pin "21") (pinfunction "SDO_21") (pintype "bidirectional"))
    )
    (net (code "104") (name "unconnected-(U2-SHD-Pad17)") (class "Default")
      (node (ref "U2") (pin "17") (pinfunction "SHD_17") (pintype "bidirectional"))
    )
    (net (code "105") (name "unconnected-(U2-SWP-Pad18)") (class "Default")
      (node (ref "U2") (pin "18") (pinfunction "SWP_18") (pintype "bidirectional"))
    )
    (net (code "106") (name "unconnected-(U4-AD0{slash}DIO0-Pad31)") (class "Default")
      (node (ref "U4") (pin "31") (pinfunction "AD0/DIO0_31") (pintype "bidirectional"))
    )
    (net (code "107") (name "unconnected-(U4-AD1{slash}DIO1-Pad30)") (class "Default")
      (node (ref "U4") (pin "30") (pinfunction "AD1/DIO1_30") (pintype "bidirectional"))
    )
    (net (code "108") (name "unconnected-(U4-AD2{slash}DIO2-Pad29)") (class "Default")
      (node (ref "U4") (pin "29") (pinfunction "AD2/DIO2_29") (pintype "bidirectional"))
    )
    (net (code "109") (name "unconnected-(U4-AD3{slash}DIO3-Pad28)") (class "Default")
      (node (ref "U4") (pin "28") (pinfunction "AD3/DIO3_28") (pintype "bidirectional"))
    )
    (net (code "110") (name "unconnected-(U4-ASSOCIATE{slash}DIO5-Pad26)") (class "Default")
      (node (ref "U4") (pin "26") (pinfunction "ASSOCIATE/DIO5_26") (pintype "bidirectional"))
    )
    (net (code "111") (name "unconnected-(U4-DIO4-Pad23)") (class "Default")
      (node (ref "U4") (pin "23") (pinfunction "DIO4_23") (pintype "bidirectional"))
    )
    (net (code "112") (name "unconnected-(U4-DIO12-Pad5)") (class "Default")
      (node (ref "U4") (pin "5") (pinfunction "DIO12_5") (pintype "bidirectional"))
    )
    (net (code "113") (name "unconnected-(U4-ON{slash}~{SLEEP}{slash}DIO9-Pad25)") (class "Default")
      (node (ref "U4") (pin "25") (pinfunction "ON/~{SLEEP}/DIO9_25") (pintype "bidirectional"))
    )
    (net (code "114") (name "unconnected-(U4-PWM1{slash}DIO11-Pad8)") (class "Default")
      (node (ref "U4") (pin "8") (pinfunction "PWM1/DIO11_8") (pintype "bidirectional"))
    )
    (net (code "115") (name "unconnected-(U4-RF-Pad33)") (class "Default")
      (node (ref "U4") (pin "33") (pinfunction "RF_33") (pintype "bidirectional"))
    )
    (net (code "116") (name "unconnected-(U4-RSSI_PWM{slash}DIO10-Pad7)") (class "Default")
      (node (ref "U4") (pin "7") (pinfunction "RSSI_PWM/DIO10_7") (pintype "bidirectional"))
    )
    (net (code "117") (name "unconnected-(U4-SPI_~{ATTN}{slash}~{BOOTMODE}{slash}DIO19-Pad11)") (class "Default")
      (node (ref "U4") (pin "11") (pinfunction "SPI_~{ATTN}/~{BOOTMODE}/DIO19_11") (pintype "bidirectional"))
    )
    (net (code "118") (name "unconnected-(U4-~{CTS}{slash}DIO7-Pad24)") (class "Default")
      (node (ref "U4") (pin "24") (pinfunction "~{CTS}/DIO7_24") (pintype "bidirectional"))
    )
    (net (code "119") (name "unconnected-(U4-~{DTR}{slash}SLEEP_RQ{slash}DIO8-Pad9)") (class "Default")
      (node (ref "U4") (pin "9") (pinfunction "~{DTR}/SLEEP_RQ/DIO8_9") (pintype "bidirectional"))
    )
    (net (code "120") (name "unconnected-(U4-~{RTS}{slash}DIO6-Pad27)") (class "Default")
      (node (ref "U4") (pin "27") (pinfunction "~{RTS}/DIO6_27") (pintype "bidirectional"))
    )
  )
)
